# BatteryNode.net
KiCad netlist of a schematic drawn in Altium Designer
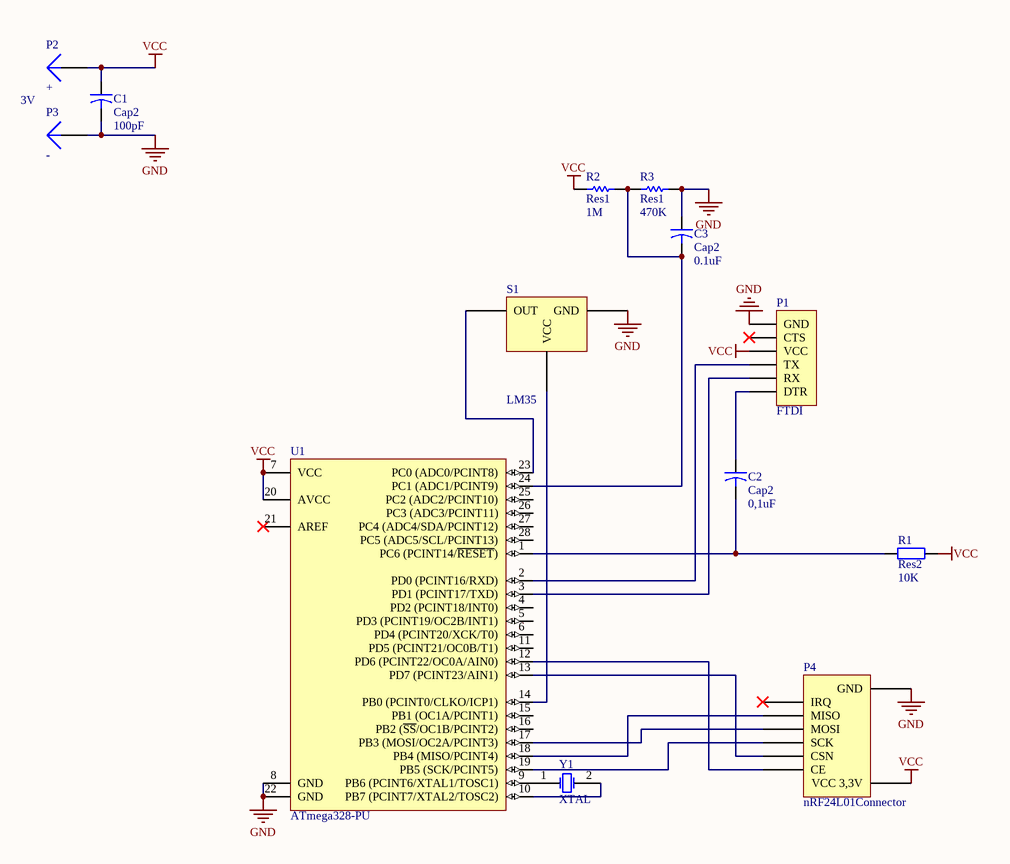
[diagram p0: BatteryNode.SchDoc]

(export (version "E")
  (design (tool "Eeschema 10.0.6"))
  (components
    (comp (ref "C1")
      (value "Cap2")
      (footprint "CAPR5-4X5")
      (description "Capacitor")
      (fields (field (name "ALTIUM_VALUE") "100pF") (field (name "PUBLISHER") "Altium Limited"))
      (libsource (lib "Miscellaneous Devices") (part "Cap2"))
    )
    (comp (ref "C2")
      (value "Cap2")
      (footprint "CAPR5-4X5")
      (description "Capacitor")
      (fields (field (name "ALTIUM_VALUE") "0,1uF") (field (name "PUBLISHER") "Altium Limited"))
      (libsource (lib "Miscellaneous Devices") (part "Cap2"))
    )
    (comp (ref "C3")
      (value "Cap2")
      (footprint "CAPR5-4X5")
      (description "Capacitor")
      (fields (field (name "ALTIUM_VALUE") "0.1uF") (field (name "PUBLISHER") "Altium Limited"))
      (libsource (lib "Miscellaneous Devices") (part "Cap2"))
    )
    (comp (ref "P1")
      (value "FTDI")
      (footprint "HDR1X6")
      (description "Header, 6-Pin")
      (fields (field (name "PUBLISHER") "Altium Limited"))
      (libsource (lib "Miscellaneous Connectors") (part "Header 6"))
    )
    (comp (ref "P2")
      (value "+")
      (footprint "PIN1")
      (description "Plug")
      (fields (field (name "PUBLISHER") "Altium Limited"))
      (libsource (lib "Miscellaneous Connectors") (part "Plug"))
    )
    (comp (ref "P3")
      (value "-")
      (footprint "PIN1")
      (description "Plug")
      (fields (field (name "PUBLISHER") "Altium Limited"))
      (libsource (lib "Miscellaneous Connectors") (part "Plug"))
    )
    (comp (ref "P4")
      (value "nRF24L01Connector")
      (footprint "HDR2X4")
      (libsource (lib "nRF24L01Connector") (part "nRF24L01Connector"))
    )
    (comp (ref "R1")
      (value "Res2")
      (footprint "AXIAL-0.4")
      (description "Resistor")
      (fields (field (name "ALTIUM_VALUE") "10K") (field (name "PUBLISHER") "Altium Limited"))
      (libsource (lib "Miscellaneous Devices") (part "Res2"))
    )
    (comp (ref "R2")
      (value "Res1")
      (footprint "AXIAL-0.3")
      (description "Resistor")
      (fields (field (name "ALTIUM_VALUE") "1M") (field (name "PUBLISHER") "Altium Limited"))
      (libsource (lib "Miscellaneous Devices") (part "Res1"))
    )
    (comp (ref "R3")
      (value "Res1")
      (footprint "AXIAL-0.3")
      (description "Resistor")
      (fields (field (name "ALTIUM_VALUE") "470K") (field (name "PUBLISHER") "Altium Limited"))
      (libsource (lib "Miscellaneous Devices") (part "Res1"))
    )
    (comp (ref "S1") (value "LM35") (footprint "TO-92") (libsource (lib "LM35") (part "LM35")))
    (comp (ref "U1")
      (value "ATmega328-PU")
      (footprint "28P3")
      (fields (field (name "PUBLISHER") "Altium Limited"))
      (libsource (lib "Atmel Microcontroller 8-Bit megaAVR") (part "ATmega328-PU"))
    )
    (comp (ref "Y1")
      (value "XTAL")
      (footprint "R38")
      (description "Crystal Oscillator")
      (fields (field (name "PUBLISHER") "Altium Limited"))
      (libsource (lib "Miscellaneous Devices") (part "XTAL"))
    )
  )
  (nets
    (net (code "1") (name "GND") (class "Default")
      (node (ref "C1") (pin "2") (pinfunction "2_2") (pintype "passive"))
      (node (ref "C3") (pin "1") (pinfunction "1_1") (pintype "passive"))
      (node (ref "P1") (pin "1") (pinfunction "GND_1") (pintype "passive"))
      (node (ref "P3") (pin "1") (pinfunction "1_1") (pintype "passive"))
      (node (ref "P4") (pin "2") (pinfunction "GND_2") (pintype "passive"))
      (node (ref "R3") (pin "2") (pinfunction "2_2") (pintype "passive"))
      (node (ref "S1") (pin "3") (pinfunction "GND_3") (pintype "passive"))
      (node (ref "U1") (pin "22") (pinfunction "GND_22") (pintype "power_in"))
      (node (ref "U1") (pin "8") (pinfunction "GND_8") (pintype "power_in"))
    )
    (net (code "2") (name "Net-(P1-DTR)") (class "Default")
      (node (ref "C2") (pin "1") (pinfunction "1_1") (pintype "passive"))
      (node (ref "P1") (pin "6") (pinfunction "DTR_6") (pintype "passive"))
    )
    (net (code "3") (name "Net-(P1-RX)") (class "Default")
      (node (ref "P1") (pin "5") (pinfunction "RX_5") (pintype "passive"))
      (node (ref "U1") (pin "3") (pinfunction "PD1_(PCINT17/TXD)_3") (pintype "bidirectional"))
    )
    (net (code "4") (name "Net-(P1-TX)") (class "Default")
      (node (ref "P1") (pin "4") (pinfunction "TX_4") (pintype "passive"))
      (node (ref "U1") (pin "2") (pinfunction "PD0_(PCINT16/RXD)_2") (pintype "bidirectional"))
    )
    (net (code "5") (name "Net-(P4-CE)") (class "Default")
      (node (ref "P4") (pin "3") (pinfunction "CE_3") (pintype "passive"))
      (node (ref "U1") (pin "12") (pinfunction "PD6_(PCINT22/OC0A/AIN0)_12") (pintype "bidirectional"))
    )
    (net (code "6") (name "Net-(P4-CSN)") (class "Default")
      (node (ref "P4") (pin "4") (pinfunction "CSN_4") (pintype "passive"))
      (node (ref "U1") (pin "13") (pinfunction "PD7_(PCINT23/AIN1)_13") (pintype "bidirectional"))
    )
    (net (code "7") (name "Net-(P4-MISO)") (class "Default")
      (node (ref "P4") (pin "7") (pinfunction "MISO_7") (pintype "passive"))
      (node (ref "U1") (pin "18") (pinfunction "PB4_(MISO/PCINT4)_18") (pintype "bidirectional"))
    )
    (net (code "8") (name "Net-(P4-MOSI)") (class "Default")
      (node (ref "P4") (pin "6") (pinfunction "MOSI_6") (pintype "passive"))
      (node (ref "U1") (pin "17") (pinfunction "PB3_(MOSI/OC2A/PCINT3)_17") (pintype "bidirectional"))
    )
    (net (code "9") (name "Net-(P4-SCK)") (class "Default")
      (node (ref "P4") (pin "5") (pinfunction "SCK_5") (pintype "passive"))
      (node (ref "U1") (pin "19") (pinfunction "PB5_(SCK/PCINT5)_19") (pintype "bidirectional"))
    )
    (net (code "10") (name "Net-(S1-OUT)") (class "Default")
      (node (ref "S1") (pin "2") (pinfunction "OUT_2") (pintype "passive"))
      (node (ref "U1") (pin "23") (pinfunction "PC0_(ADC0/PCINT8)_23") (pintype "bidirectional"))
    )
    (net (code "11") (name "Net-(S1-VCC)") (class "Default")
      (node (ref "S1") (pin "1") (pinfunction "VCC_1") (pintype "passive"))
      (node (ref "U1") (pin "14") (pinfunction "PB0_(PCINT0/CLKO/ICP1)_14") (pintype "bidirectional"))
    )
    (net (code "12") (name "Net-(U1-PB6_(PCINT6{slash}XTAL1{slash}TOSC1))") (class "Default")
      (node (ref "U1") (pin "9") (pinfunction "PB6_(PCINT6/XTAL1/TOSC1)_9") (pintype "bidirectional"))
      (node (ref "Y1") (pin "1") (pinfunction "OSC1_1") (pintype "passive"))
    )
    (net (code "13") (name "Net-(U1-PB7_(PCINT7{slash}XTAL2{slash}TOSC2))") (class "Default")
      (node (ref "U1") (pin "10") (pinfunction "PB7_(PCINT7/XTAL2/TOSC2)_10") (pintype "bidirectional"))
      (node (ref "Y1") (pin "2") (pinfunction "OSC2_2") (pintype "passive"))
    )
    (net (code "14") (name "Net-(U1-PC1_(ADC1{slash}PCINT9))") (class "Default")
      (node (ref "C3") (pin "2") (pinfunction "2_2") (pintype "passive"))
      (node (ref "R2") (pin "2") (pinfunction "2_2") (pintype "passive"))
      (node (ref "R3") (pin "1") (pinfunction "1_1") (pintype "passive"))
      (node (ref "U1") (pin "24") (pinfunction "PC1_(ADC1/PCINT9)_24") (pintype "bidirectional"))
    )
    (net (code "15") (name "Net-(U1-PC6_(PCINT14{slash}~{RESET}))") (class "Default")
      (node (ref "C2") (pin "2") (pinfunction "2_2") (pintype "passive"))
      (node (ref "R1") (pin "1") (pinfunction "1_1") (pintype "passive"))
      (node (ref "U1") (pin "1") (pinfunction "PC6_(PCINT14/~{RESET})_1") (pintype "bidirectional"))
    )
    (net (code "16") (name "VCC") (class "Default")
      (node (ref "C1") (pin "1") (pinfunction "1_1") (pintype "passive"))
      (node (ref "P1") (pin "3") (pinfunction "VCC_3") (pintype "passive"))
      (node (ref "P2") (pin "1") (pinfunction "1_1") (pintype "passive"))
      (node (ref "P4") (pin "1") (pinfunction "VCC_3,3V_1") (pintype "passive"))
      (node (ref "R1") (pin "2") (pinfunction "2_2") (pintype "passive"))
      (node (ref "R2") (pin "1") (pinfunction "1_1") (pintype "passive"))
      (node (ref "U1") (pin "20") (pinfunction "AVCC_20") (pintype "power_in"))
      (node (ref "U1") (pin "7") (pinfunction "VCC_7") (pintype "power_in"))
    )
    (net (code "17") (name "unconnected-(P1-CTS-Pad2)") (class "Default")
      (node (ref "P1") (pin "2") (pinfunction "CTS_2") (pintype "passive+no_connect"))
    )
    (net (code "18") (name "unconnected-(P4-IRQ-Pad8)") (class "Default")
      (node (ref "P4") (pin "8") (pinfunction "IRQ_8") (pintype "passive+no_connect"))
    )
    (net (code "19") (name "unconnected-(U1-AREF-Pad21)") (class "Default")
      (node (ref "U1") (pin "21") (pinfunction "AREF_21") (pintype "power_in+no_connect"))
    )
    (net (code "20") (name "unconnected-(U1-PB1_(OC1A{slash}PCINT1)-Pad15)") (class "Default")
      (node (ref "U1") (pin "15") (pinfunction "PB1_(OC1A/PCINT1)_15") (pintype "bidirectional"))
    )
    (net (code "21") (name "unconnected-(U1-PB2_(~{SS}{slash}OC1B{slash}PCINT2)-Pad16)") (class "Default")
      (node (ref "U1") (pin "16") (pinfunction "PB2_(~{SS}/OC1B/PCINT2)_16") (pintype "bidirectional"))
    )
    (net (code "22") (name "unconnected-(U1-PC2_(ADC2{slash}PCINT10)-Pad25)") (class "Default")
      (node (ref "U1") (pin "25") (pinfunction "PC2_(ADC2/PCINT10)_25") (pintype "bidirectional"))
    )
    (net (code "23") (name "unconnected-(U1-PC3_(ADC3{slash}PCINT11)-Pad26)") (class "Default")
      (node (ref "U1") (pin "26") (pinfunction "PC3_(ADC3/PCINT11)_26") (pintype "bidirectional"))
    )
    (net (code "24") (name "unconnected-(U1-PC4_(ADC4{slash}SDA{slash}PCINT12)-Pad27)") (class "Default")
      (node (ref "U1") (pin "27") (pinfunction "PC4_(ADC4/SDA/PCINT12)_27") (pintype "bidirectional"))
    )
    (net (code "25") (name "unconnected-(U1-PC5_(ADC5{slash}SCL{slash}PCINT13)-Pad28)") (class "Default")
      (node (ref "U1") (pin "28") (pinfunction "PC5_(ADC5/SCL/PCINT13)_28") (pintype "bidirectional"))
    )
    (net (code "26") (name "unconnected-(U1-PD2_(PCINT18{slash}INT0)-Pad4)") (class "Default")
      (node (ref "U1") (pin "4") (pinfunction "PD2_(PCINT18/INT0)_4") (pintype "bidirectional"))
    )
    (net (code "27") (name "unconnected-(U1-PD3_(PCINT19{slash}OC2B{slash}INT1)-Pad5)") (class "Default")
      (node (ref "U1") (pin "5") (pinfunction "PD3_(PCINT19/OC2B/INT1)_5") (pintype "bidirectional"))
    )
    (net (code "28") (name "unconnected-(U1-PD4_(PCINT20{slash}XCK{slash}T0)-Pad6)") (class "Default")
      (node (ref "U1") (pin "6") (pinfunction "PD4_(PCINT20/XCK/T0)_6") (pintype "bidirectional"))
    )
    (net (code "29") (name "unconnected-(U1-PD5_(PCINT21{slash}OC0B{slash}T1)-Pad11)") (class "Default")
      (node (ref "U1") (pin "11") (pinfunction "PD5_(PCINT21/OC0B/T1)_11") (pintype "bidirectional"))
    )
  )
)
